# msl.net
KiCad netlist of a schematic drawn in EAGLE
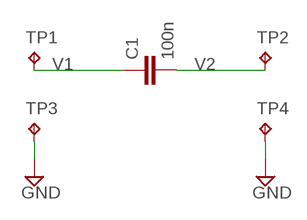
[diagram p0: schematic, sheet 1]

(export (version "E")
  (design (tool "Eeschema 10.0.6"))
  (components
    (comp (ref "C1")
      (value "100n")
      (footprint "eagle-import:C0402K")
      (libsource (lib "eagle-import") (part "C-EUC0402K"))
    )
    (comp (ref "TP1")
      (value "TPTP06SQ")
      (footprint "eagle-import:TP06SQ")
      (libsource (lib "eagle-import") (part "TPTP06SQ"))
    )
    (comp (ref "TP2")
      (value "TPTP06SQ")
      (footprint "eagle-import:TP06SQ")
      (libsource (lib "eagle-import") (part "TPTP06SQ"))
    )
    (comp (ref "TP3")
      (value "TPTP06SQ")
      (footprint "eagle-import:TP06SQ")
      (libsource (lib "eagle-import") (part "TPTP06SQ"))
    )
    (comp (ref "TP4")
      (value "TPTP06SQ")
      (footprint "eagle-import:TP06SQ")
      (libsource (lib "eagle-import") (part "TPTP06SQ"))
    )
  )
  (nets
    (net (code "1") (name "/V1") (class "Default")
      (node (ref "C1") (pin "1") (pinfunction "1_1") (pintype "passive"))
      (node (ref "TP1") (pin "TP") (pinfunction "TP_TP") (pintype "input"))
    )
    (net (code "2") (name "/V2") (class "Default")
      (node (ref "C1") (pin "2") (pinfunction "2_2") (pintype "passive"))
      (node (ref "TP2") (pin "TP") (pinfunction "TP_TP") (pintype "input"))
    )
    (net (code "3") (name "GND") (class "Default")
      (node (ref "TP3") (pin "TP") (pinfunction "TP_TP") (pintype "input"))
      (node (ref "TP4") (pin "TP") (pinfunction "TP_TP") (pintype "input"))
    )
  )
)
